# 01_power.net
KiCad netlist of a schematic drawn in Altium Designer
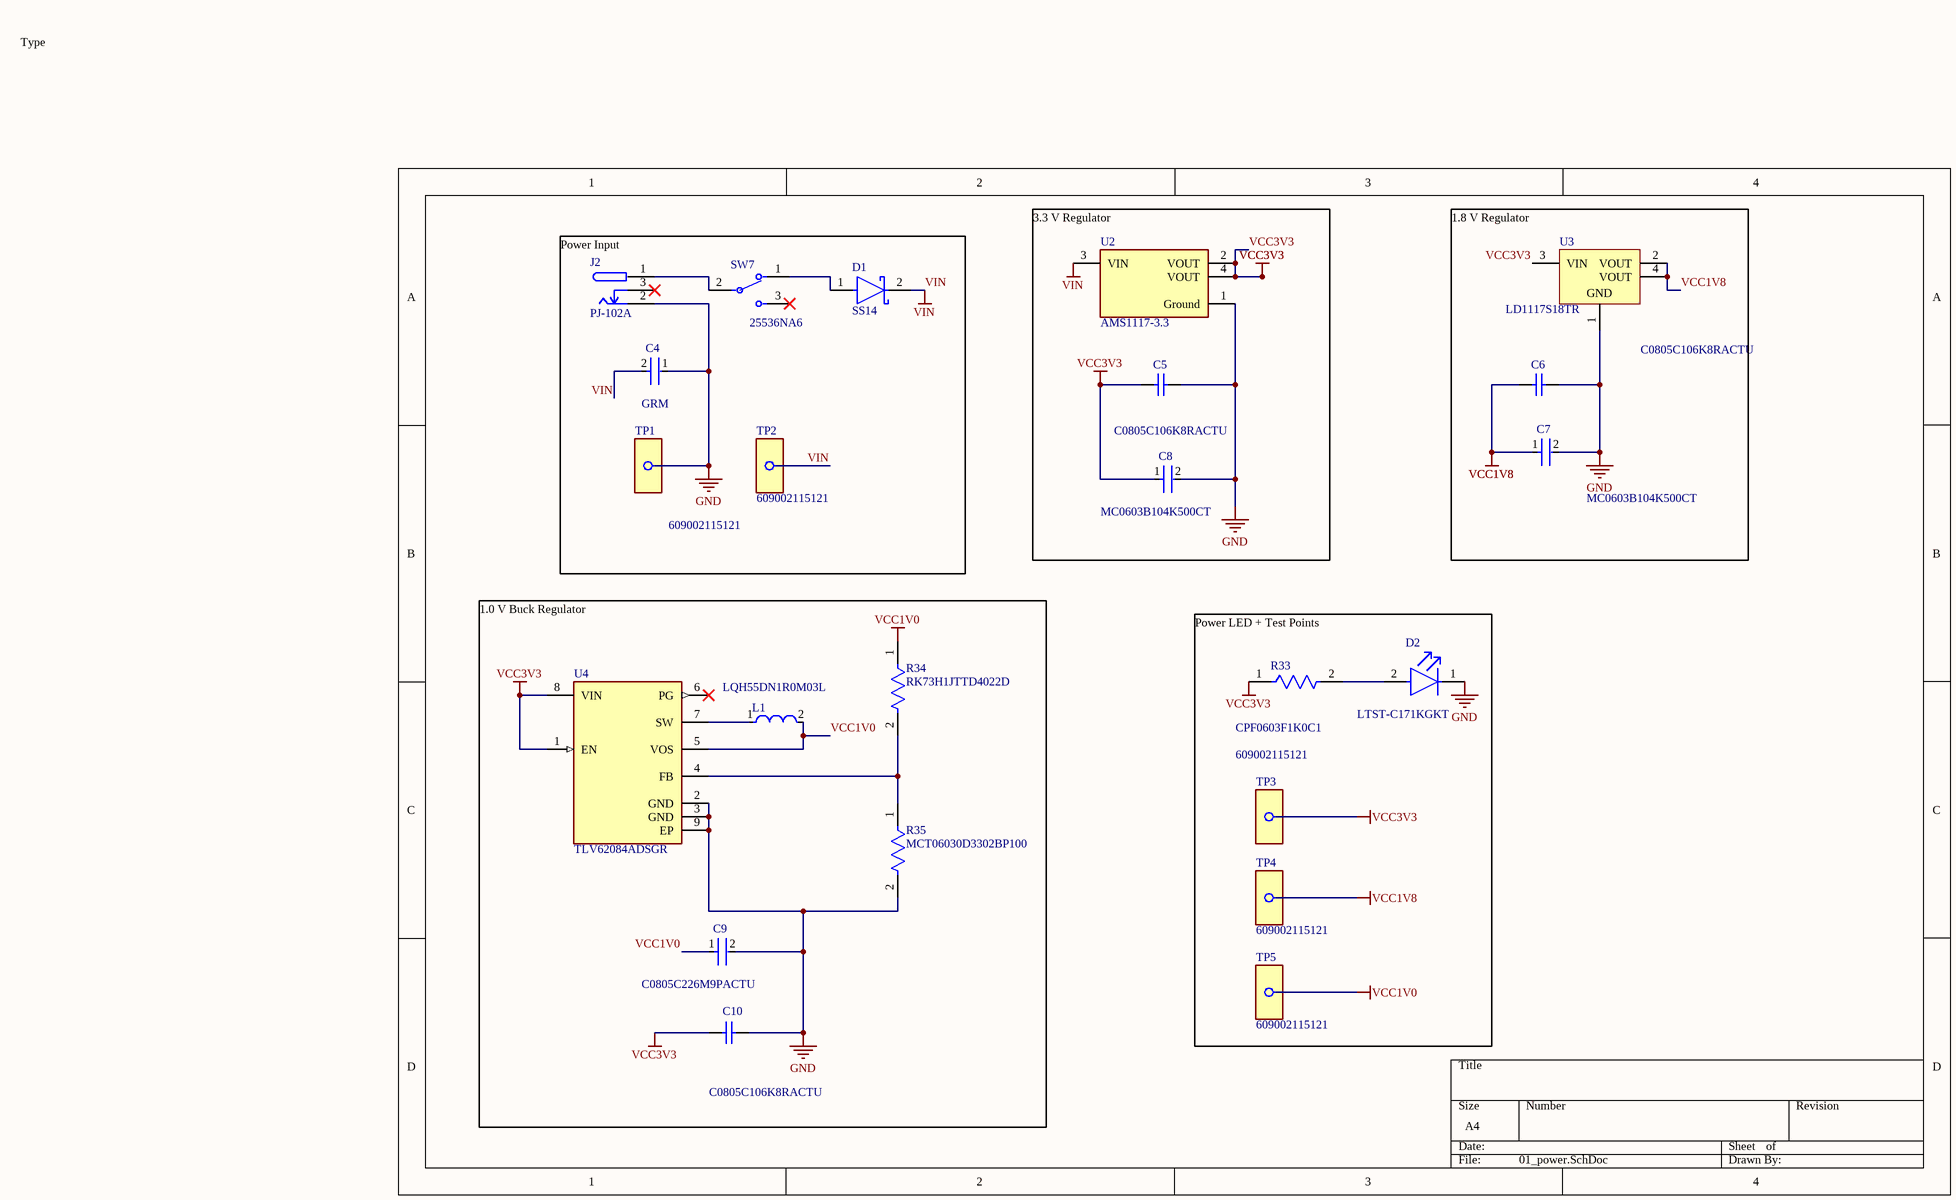
[diagram p0: 01_power.SchDoc]

(export (version "E")
  (design (tool "Eeschema 10.0.6"))
  (components
    (comp (ref "C4")
      (value "GRM")
      (footprint "FP-GRM31C-0_3-e0_3_0_8-IPC_C")
      (description "Chip Multilayer Ceramic Capacitors for General Purpose, 1206, 47uF, X5R, 15%, 20%, 16V")
      (fields (field (name "TOLERANCE") "20%"))
      (libsource (lib "Altium Content Vault") (part "f23184f103b6ebe33a8c269c53dcba6"))
    )
    (comp (ref "C5")
      (value "C0805C106K8RACTU")
      (footprint "CAPC2013X145X50LL20T25")
      (fields (field (name "MANUFACTURER") "Kemet"))
      (libsource (lib "Altium Content Vault") (part "CAP"))
    )
    (comp (ref "C6")
      (value "C0805C106K8RACTU")
      (footprint "CAPC2013X145X50LL20T25")
      (fields (field (name "MANUFACTURER") "Kemet"))
      (libsource (lib "Altium Content Vault") (part "CAP"))
    )
    (comp (ref "C7")
      (value "MC0603B104K500CT")
      (footprint "FP-MC0603-IPC_C")
      (description "Ceramic Capacitor, Multilayer, Ceramic, 50V, 10% +Tol, 10% -Tol, X7R, -/+15ppm/Cel TC, 0.1uF, 0603")
      (fields (field (name "TOLERANCE") "10%"))
      (libsource (lib "Altium Content Vault") (part "b4654b650e69147ec39a6b967a45e02"))
    )
    (comp (ref "C8")
      (value "MC0603B104K500CT")
      (footprint "FP-MC0603-IPC_C")
      (description "Ceramic Capacitor, Multilayer, Ceramic, 50V, 10% +Tol, 10% -Tol, X7R, -/+15ppm/Cel TC, 0.1uF, 0603")
      (fields (field (name "TOLERANCE") "10%"))
      (libsource (lib "Altium Content Vault") (part "b4654b650e69147ec39a6b967a45e02"))
    )
    (comp (ref "C9")
      (value "C0805C226M9PACTU")
      (footprint "FP-C0805C226M9PACTU-MFG")
      (description "CAP CER 22UF 6.3V X5R 0805")
      (fields (field (name "TOLERANCE") "20%") (field (name "VOLTAGE") "6.3V"))
      (libsource (lib "Altium Content Vault") (part "11868f565c42a9108669ba33697ecf6"))
    )
    (comp (ref "C10")
      (value "C0805C106K8RACTU")
      (footprint "CAPC2013X145X50LL20T25")
      (fields (field (name "MANUFACTURER") "Kemet"))
      (libsource (lib "Altium Content Vault") (part "CAP"))
    )
    (comp (ref "D1")
      (value "SS14")
      (footprint "FP-403AE-MFG")
      (description "DIODE SCHOTTKY 40V 1A SMA")
      (fields
        (field (name "MANUFACTURER") "ON Semiconductor")
        (field (name "OCTOPART") "https://octopart.com/ss14-on+semiconductor-29205033")
      )
      (libsource (lib "Altium Content Vault") (part "360ad2f4ac25a952324d13796385471"))
    )
    (comp (ref "D2")
      (value "LTST-C171KGKT")
      (footprint "FP-LTST-C171KGKT-MFG")
      (description "LED GREEN CLEAR SMD")
      (libsource (lib "Altium Content Vault") (part "8706943c75ba83719d021d2fdc84c58"))
    )
    (comp (ref "J2")
      (value "PJ-102A")
      (footprint "FP-PJ-102A-MFG")
      (description "PJ-102A 2.0 x 6.5 mm, 2.5 A, Horizontal, Through Hole, Tapered Pins, Dc Power Jack Connector")
      (libsource (lib "Altium Content Vault") (part "c639f672d24b5d70918fa8d934b95d1"))
    )
    (comp (ref "L1")
      (value "LQH55DN1R0M03L")
      (footprint "FP-LQH55DN_03-MFG")
      (description "Wire Wound Ferrite Inductor for Power Lines 1μH ±20% 0.0266Ω  4.0A 2220")
      (fields (field (name "TOLERANCE") "20%"))
      (libsource (lib "Altium Content Vault") (part "725321dda6339637d4d059423bc1c3c"))
    )
    (comp (ref "R33")
      (value "CPF0603F1K0C1")
      (footprint "FP-CPF0603-MFG")
      (description "RES SMD 1.0KΩ 1% 1/16W 0603")
      (fields
        (field (name "OCTOPART") "https://octopart.com/cpf0603f1k0c1-te+connectivity-42013134")
        (field (name "TOLERANCE") "1%")
      )
      (libsource (lib "Altium Content Vault") (part "1029c3af85768c4190bb7ad29bc67b5"))
    )
    (comp (ref "R34")
      (value "RK73H1JTTD4022D")
      (footprint "FP-RK73H1J-MFG")
      (description "40.2kΩ ±0.5% 0.1W Chip Resistor 0603 Thick Film AEC-Q200 Qualified")
      (fields (field (name "TOLERANCE") "0.5%"))
      (libsource (lib "Altium Content Vault") (part "1029c3af85768c4190bb7ad29bc67b5"))
    )
    (comp (ref "R35")
      (value "MCT06030D3302BP100")
      (footprint "FP-MCT0603-IPC_B")
      (description "RES SMD 100 OHM 1% 1/8W 0603")
      (fields (field (name "TOLERANCE") "0.1%"))
      (libsource (lib "Altium Content Vault") (part "1029c3af85768c4190bb7ad29bc67b5"))
    )
    (comp (ref "SW7")
      (value "25536NA6")
      (footprint "FP-25536NA6-0")
      (description "SWITCH SLIDE SPDT 4A 125V")
      (libsource (lib "Altium Content Vault") (part "52c419afdc2a387c7d548259a9aeefb"))
    )
    (comp (ref "TP1")
      (value "609002115121")
      (footprint "FP-609002115121-MFG")
      (description "WR-PHD_2.54MM_JUMPER_BLACK W/ TE")
      (libsource (lib "Altium Content Vault") (part "49ac5b8c93fd98546550e1ad307e158"))
    )
    (comp (ref "TP2")
      (value "609002115121")
      (footprint "FP-609002115121-MFG")
      (description "WR-PHD_2.54MM_JUMPER_BLACK W/ TE")
      (libsource (lib "Altium Content Vault") (part "49ac5b8c93fd98546550e1ad307e158"))
    )
    (comp (ref "TP3")
      (value "609002115121")
      (footprint "FP-609002115121-MFG")
      (description "WR-PHD_2.54MM_JUMPER_BLACK W/ TE")
      (libsource (lib "Altium Content Vault") (part "49ac5b8c93fd98546550e1ad307e158"))
    )
    (comp (ref "TP4")
      (value "609002115121")
      (footprint "FP-609002115121-MFG")
      (description "WR-PHD_2.54MM_JUMPER_BLACK W/ TE")
      (libsource (lib "Altium Content Vault") (part "49ac5b8c93fd98546550e1ad307e158"))
    )
    (comp (ref "TP5")
      (value "609002115121")
      (footprint "FP-609002115121-MFG")
      (description "WR-PHD_2.54MM_JUMPER_BLACK W/ TE")
      (libsource (lib "Altium Content Vault") (part "49ac5b8c93fd98546550e1ad307e158"))
    )
    (comp (ref "U2")
      (value "AMS1117-3.3")
      (footprint "FP-AMS1117-IPC_C")
      (description "LDO Voltage Regulators 1A, 3.3V")
      (fields
        (field (name "OCTOPART") "https://octopart.com/ams1117-3.3-advanced+monolithic+systems-25899300")
        (field (name "MANUFACTURER") "Advanced Monolithic Systems")
      )
      (libsource (lib "Altium Content Vault") (part "8bdbb5f8e77002000e30dd2845d0354"))
    )
    (comp (ref "U3")
      (value "LD1117S18TR")
      (footprint "SOT-223_M")
      (description "Fixed Low Drop Positive Voltage Regulator, 1.8V, 4-Pin SOT-223, Tape and Reel")
      (libsource (lib "Altium Content Vault") (part "PM-REG-LD1117-SOT4"))
    )
    (comp (ref "U4")
      (value "TLV62084ADSGR")
      (footprint "FP-DSG0008A-IPC_C")
      (description "IC REG BUCK ADJUSTABLE 2A 8WSON")
      (libsource (lib "Altium Content Vault") (part "57b80c175f452fde129af6a297e997f"))
    )
  )
  (nets
    (net (code "1") (name "GND") (class "Default")
      (node (ref "C10") (pin "2") (pinfunction "2_2") (pintype "passive"))
      (node (ref "C4") (pin "1") (pinfunction "1_1") (pintype "passive"))
      (node (ref "C5") (pin "2") (pinfunction "2_2") (pintype "passive"))
      (node (ref "C6") (pin "2") (pinfunction "2_2") (pintype "passive"))
      (node (ref "C7") (pin "2") (pinfunction "2_2") (pintype "passive"))
      (node (ref "C8") (pin "2") (pinfunction "2_2") (pintype "passive"))
      (node (ref "C9") (pin "2") (pinfunction "2_2") (pintype "passive"))
      (node (ref "D2") (pin "1") (pinfunction "C_1") (pintype "passive"))
      (node (ref "J2") (pin "2") (pinfunction "2_2") (pintype "passive"))
      (node (ref "R35") (pin "2") (pinfunction "2_2") (pintype "passive"))
      (node (ref "U2") (pin "1") (pinfunction "Ground_1") (pintype "power_in"))
      (node (ref "U3") (pin "1") (pinfunction "GND_1") (pintype "power_in"))
      (node (ref "U4") (pin "2") (pinfunction "GND_2") (pintype "power_in"))
      (node (ref "U4") (pin "3") (pinfunction "GND_3") (pintype "power_in"))
      (node (ref "U4") (pin "9") (pinfunction "EP_9") (pintype "power_in"))
    )
    (net (code "2") (name "Net-(D1-A)") (class "Default")
      (node (ref "D1") (pin "1") (pinfunction "A_1") (pintype "passive"))
      (node (ref "SW7") (pin "1") (pinfunction "1_1") (pintype "passive"))
    )
    (net (code "3") (name "Net-(D2-A)") (class "Default")
      (node (ref "D2") (pin "2") (pinfunction "A_2") (pintype "passive"))
      (node (ref "R33") (pin "2") (pinfunction "2_2") (pintype "passive"))
    )
    (net (code "4") (name "Net-(J2-Pad1)") (class "Default")
      (node (ref "J2") (pin "1") (pinfunction "1_1") (pintype "passive"))
      (node (ref "SW7") (pin "2") (pinfunction "2_2") (pintype "passive"))
    )
    (net (code "5") (name "Net-(U4-FB)") (class "Default")
      (node (ref "R34") (pin "2") (pinfunction "2_2") (pintype "passive"))
      (node (ref "R35") (pin "1") (pinfunction "1_1") (pintype "passive"))
      (node (ref "U4") (pin "4") (pinfunction "FB_4") (pintype "passive"))
    )
    (net (code "6") (name "Net-(U4-SW)") (class "Default")
      (node (ref "L1") (pin "1") (pinfunction "1_1") (pintype "passive"))
      (node (ref "U4") (pin "7") (pinfunction "SW_7") (pintype "power_in"))
    )
    (net (code "7") (name "VCC1V0") (class "Default")
      (node (ref "C9") (pin "1") (pinfunction "1_1") (pintype "passive"))
      (node (ref "L1") (pin "2") (pinfunction "2_2") (pintype "passive"))
      (node (ref "R34") (pin "1") (pinfunction "1_1") (pintype "passive"))
      (node (ref "U4") (pin "5") (pinfunction "VOS_5") (pintype "passive"))
    )
    (net (code "8") (name "VCC1V8") (class "Default")
      (node (ref "C6") (pin "1") (pinfunction "1_1") (pintype "passive"))
      (node (ref "C7") (pin "1") (pinfunction "1_1") (pintype "passive"))
      (node (ref "U3") (pin "2") (pinfunction "VOUT_2") (pintype "power_in"))
      (node (ref "U3") (pin "4") (pinfunction "VOUT_4") (pintype "power_in"))
    )
    (net (code "9") (name "VCC3V3") (class "Default")
      (node (ref "C10") (pin "1") (pinfunction "1_1") (pintype "passive"))
      (node (ref "C5") (pin "1") (pinfunction "1_1") (pintype "passive"))
      (node (ref "C8") (pin "1") (pinfunction "1_1") (pintype "passive"))
      (node (ref "R33") (pin "1") (pinfunction "1_1") (pintype "passive"))
      (node (ref "U2") (pin "2") (pinfunction "VOUT_2") (pintype "passive"))
      (node (ref "U2") (pin "4") (pinfunction "VOUT_4") (pintype "passive"))
      (node (ref "U3") (pin "3") (pinfunction "VIN_3") (pintype "power_in"))
      (node (ref "U4") (pin "1") (pinfunction "EN_1") (pintype "input"))
      (node (ref "U4") (pin "8") (pinfunction "VIN_8") (pintype "power_in"))
    )
    (net (code "10") (name "VIN") (class "Default")
      (node (ref "C4") (pin "2") (pinfunction "2_2") (pintype "passive"))
      (node (ref "D1") (pin "2") (pinfunction "C_2") (pintype "passive"))
      (node (ref "U2") (pin "3") (pinfunction "VIN_3") (pintype "power_in"))
    )
    (net (code "11") (name "unconnected-(J2-Pad3)") (class "Default")
      (node (ref "J2") (pin "3") (pinfunction "3_3") (pintype "passive+no_connect"))
    )
    (net (code "12") (name "unconnected-(SW7-Pad3)") (class "Default")
      (node (ref "SW7") (pin "3") (pinfunction "3_3") (pintype "passive+no_connect"))
    )
    (net (code "13") (name "unconnected-(U4-PG-Pad6)") (class "Default")
      (node (ref "U4") (pin "6") (pinfunction "PG_6") (pintype "output+no_connect"))
    )
  )
)
